# CW308_K82.net
KiCad netlist of a schematic drawn in Altium Designer
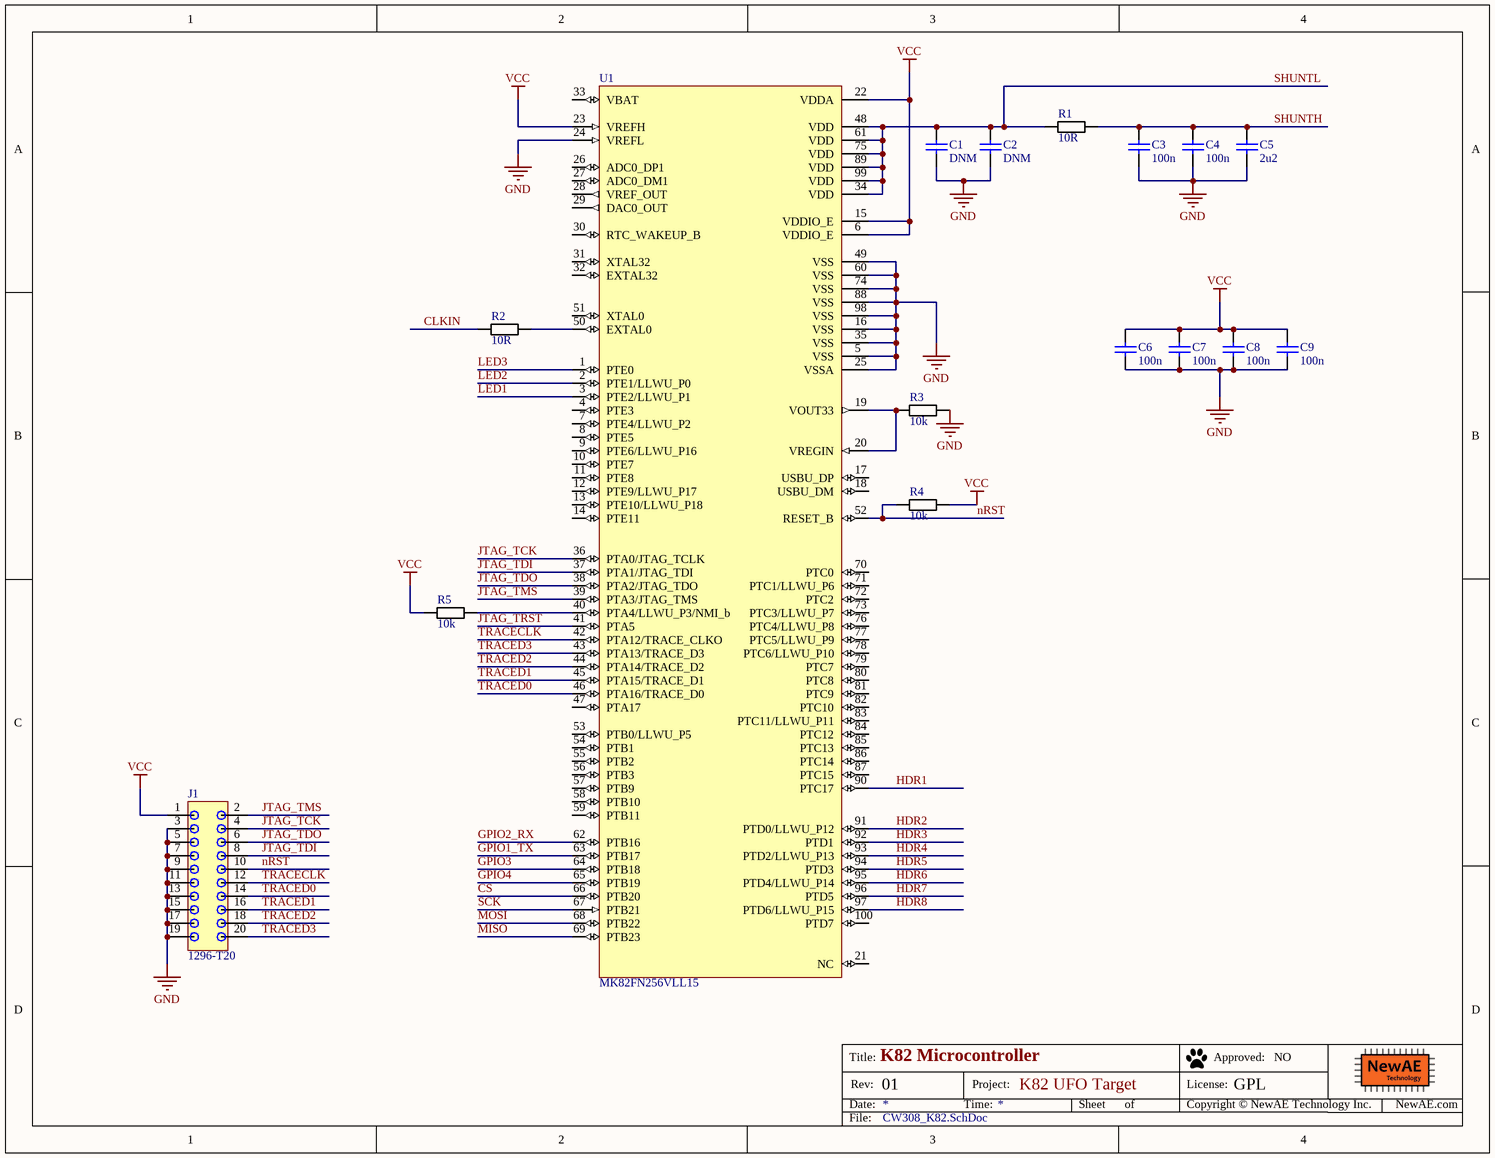
[diagram p0: CW308_K82.SchDoc]

(export (version "E")
  (design (tool "Eeschema 10.0.6"))
  (components
    (comp (ref "C1")
      (value "DNM")
      (footprint "CAPC0603_M")
      (fields (field (name "PART NUMBER") "CCHIP-100n-0603"))
      (libsource (lib "NewAE_AltiumLib") (part "CAP"))
    )
    (comp (ref "C2")
      (value "DNM")
      (footprint "CAPC0603_M")
      (fields (field (name "PART NUMBER") "CCHIP-100n-0603"))
      (libsource (lib "NewAE_AltiumLib") (part "CAP"))
    )
    (comp (ref "C3")
      (value "100n")
      (footprint "CAPC0603_M")
      (description "100n, 0603")
      (fields (field (name "PART NUMBER") "CCHIP-100n-0603"))
      (libsource (lib "NewAE_AltiumLib") (part "CAP"))
    )
    (comp (ref "C4")
      (value "100n")
      (footprint "CAPC0603_M")
      (description "100n, 0603")
      (fields (field (name "PART NUMBER") "CCHIP-100n-0603"))
      (libsource (lib "NewAE_AltiumLib") (part "CAP"))
    )
    (comp (ref "C5")
      (value "2u2")
      (footprint "CAPC0603_M")
      (description "2u2, 0603")
      (fields (field (name "PART NUMBER") "CCHIP-2u2-0603"))
      (libsource (lib "NewAE_AltiumLib") (part "CAP"))
    )
    (comp (ref "C6")
      (value "100n")
      (footprint "CAPC0603_M")
      (description "100n, 0603")
      (fields (field (name "PART NUMBER") "CCHIP-100n-0603"))
      (libsource (lib "NewAE_AltiumLib") (part "CAP"))
    )
    (comp (ref "C7")
      (value "100n")
      (footprint "CAPC0603_M")
      (description "100n, 0603")
      (fields (field (name "PART NUMBER") "CCHIP-100n-0603"))
      (libsource (lib "NewAE_AltiumLib") (part "CAP"))
    )
    (comp (ref "C8")
      (value "100n")
      (footprint "CAPC0603_M")
      (description "100n, 0603")
      (fields (field (name "PART NUMBER") "CCHIP-100n-0603"))
      (libsource (lib "NewAE_AltiumLib") (part "CAP"))
    )
    (comp (ref "C9")
      (value "100n")
      (footprint "CAPC0603_M")
      (description "100n, 0603")
      (fields (field (name "PART NUMBER") "CCHIP-100n-0603"))
      (libsource (lib "NewAE_AltiumLib") (part "CAP"))
    )
    (comp (ref "J1")
      (value "1296-T20")
      (footprint "1296-T20")
      (description "Header, 20-pin, SMD, 0.05\"")
      (libsource (lib "NewAE_AltiumLib") (part "CON20_2ROW"))
    )
    (comp (ref "R1")
      (value "10R")
      (footprint "RESC1608X55N")
      (description "10R res, 0603, 1%, 1/10W")
      (fields (field (name "PART NUMBER") "RCHIP-10R-0603") (field (name "TOLERANCE") "1%"))
      (libsource (lib "NewAE_AltiumLib") (part "RES-EU"))
    )
    (comp (ref "R2")
      (value "10R")
      (footprint "RESC1608X55N")
      (description "10R res, 0603, 1%, 1/10W")
      (fields (field (name "PART NUMBER") "RCHIP-10R-0603") (field (name "TOLERANCE") "1%"))
      (libsource (lib "NewAE_AltiumLib") (part "RES-EU"))
    )
    (comp (ref "R3")
      (value "10k")
      (footprint "RESC1608X55N")
      (description "10k res, 0603, 1%, 1/10W")
      (fields (field (name "PART NUMBER") "RCHIP-10K-0603") (field (name "TOLERANCE") "1%"))
      (libsource (lib "NewAE_AltiumLib") (part "RES-EU"))
    )
    (comp (ref "R4")
      (value "10k")
      (footprint "RESC1608X55N")
      (description "10k res, 0603, 1%, 1/10W")
      (fields (field (name "PART NUMBER") "RCHIP-10K-0603") (field (name "TOLERANCE") "1%"))
      (libsource (lib "NewAE_AltiumLib") (part "RES-EU"))
    )
    (comp (ref "R5")
      (value "10k")
      (footprint "RESC1608X55N")
      (description "10k res, 0603, 1%, 1/10W")
      (fields (field (name "PART NUMBER") "RCHIP-10K-0603") (field (name "TOLERANCE") "1%"))
      (libsource (lib "NewAE_AltiumLib") (part "RES-EU"))
    )
    (comp (ref "U1")
      (value "MK82FN256VLL15")
      (footprint "SQFP50P1600X1600X170-100N")
      (libsource (lib "NewAE_AltiumLib") (part "MK82FN256VLL15"))
    )
  )
  (nets
    (net (code "1") (name "/CLKIN") (class "Default")
      (node (ref "R2") (pin "1") (pinfunction "1_1") (pintype "passive"))
    )
    (net (code "2") (name "/CS") (class "Default")
      (node (ref "U1") (pin "66") (pinfunction "PTB20_66") (pintype "bidirectional"))
    )
    (net (code "3") (name "/GPIO1_TX") (class "Default")
      (node (ref "U1") (pin "63") (pinfunction "PTB17_63") (pintype "bidirectional"))
    )
    (net (code "4") (name "/GPIO2_RX") (class "Default")
      (node (ref "U1") (pin "62") (pinfunction "PTB16_62") (pintype "bidirectional"))
    )
    (net (code "5") (name "/GPIO3") (class "Default")
      (node (ref "U1") (pin "64") (pinfunction "PTB18_64") (pintype "bidirectional"))
    )
    (net (code "6") (name "/GPIO4") (class "Default")
      (node (ref "U1") (pin "65") (pinfunction "PTB19_65") (pintype "bidirectional"))
    )
    (net (code "7") (name "/HDR1") (class "Default")
      (node (ref "U1") (pin "90") (pinfunction "PTC17_90") (pintype "bidirectional"))
    )
    (net (code "8") (name "/HDR2") (class "Default")
      (node (ref "U1") (pin "91") (pinfunction "PTD0/LLWU_P12_91") (pintype "bidirectional"))
    )
    (net (code "9") (name "/HDR3") (class "Default")
      (node (ref "U1") (pin "92") (pinfunction "PTD1_92") (pintype "bidirectional"))
    )
    (net (code "10") (name "/HDR4") (class "Default")
      (node (ref "U1") (pin "93") (pinfunction "PTD2/LLWU_P13_93") (pintype "bidirectional"))
    )
    (net (code "11") (name "/HDR5") (class "Default")
      (node (ref "U1") (pin "94") (pinfunction "PTD3_94") (pintype "bidirectional"))
    )
    (net (code "12") (name "/HDR6") (class "Default")
      (node (ref "U1") (pin "95") (pinfunction "PTD4/LLWU_P14_95") (pintype "bidirectional"))
    )
    (net (code "13") (name "/HDR7") (class "Default")
      (node (ref "U1") (pin "96") (pinfunction "PTD5_96") (pintype "bidirectional"))
    )
    (net (code "14") (name "/HDR8") (class "Default")
      (node (ref "U1") (pin "97") (pinfunction "PTD6/LLWU_P15_97") (pintype "bidirectional"))
    )
    (net (code "15") (name "/JTAG_TCK") (class "Default")
      (node (ref "J1") (pin "4") (pinfunction "4_4") (pintype "passive"))
      (node (ref "U1") (pin "36") (pinfunction "PTA0/JTAG_TCLK_36") (pintype "bidirectional"))
    )
    (net (code "16") (name "/JTAG_TDI") (class "Default")
      (node (ref "J1") (pin "8") (pinfunction "8_8") (pintype "passive"))
      (node (ref "U1") (pin "37") (pinfunction "PTA1/JTAG_TDI_37") (pintype "bidirectional"))
    )
    (net (code "17") (name "/JTAG_TDO") (class "Default")
      (node (ref "J1") (pin "6") (pinfunction "6_6") (pintype "passive"))
      (node (ref "U1") (pin "38") (pinfunction "PTA2/JTAG_TDO_38") (pintype "bidirectional"))
    )
    (net (code "18") (name "/JTAG_TMS") (class "Default")
      (node (ref "J1") (pin "2") (pinfunction "2_2") (pintype "passive"))
      (node (ref "U1") (pin "39") (pinfunction "PTA3/JTAG_TMS_39") (pintype "bidirectional"))
    )
    (net (code "19") (name "/JTAG_TRST") (class "Default")
      (node (ref "U1") (pin "41") (pinfunction "PTA5_41") (pintype "bidirectional"))
    )
    (net (code "20") (name "/LED1") (class "Default")
      (node (ref "U1") (pin "3") (pinfunction "PTE2/LLWU_P1_3") (pintype "bidirectional"))
    )
    (net (code "21") (name "/LED2") (class "Default")
      (node (ref "U1") (pin "2") (pinfunction "PTE1/LLWU_P0_2") (pintype "bidirectional"))
    )
    (net (code "22") (name "/LED3") (class "Default")
      (node (ref "U1") (pin "1") (pinfunction "PTE0_1") (pintype "bidirectional"))
    )
    (net (code "23") (name "/MISO") (class "Default")
      (node (ref "U1") (pin "69") (pinfunction "PTB23_69") (pintype "bidirectional"))
    )
    (net (code "24") (name "/MOSI") (class "Default")
      (node (ref "U1") (pin "68") (pinfunction "PTB22_68") (pintype "bidirectional"))
    )
    (net (code "25") (name "/SCK") (class "Default")
      (node (ref "U1") (pin "67") (pinfunction "PTB21_67") (pintype "input"))
    )
    (net (code "26") (name "/SHUNTH") (class "Default")
      (node (ref "C3") (pin "1") (pinfunction "1_1") (pintype "passive"))
      (node (ref "C4") (pin "1") (pinfunction "1_1") (pintype "passive"))
      (node (ref "C5") (pin "1") (pinfunction "1_1") (pintype "passive"))
      (node (ref "R1") (pin "2") (pinfunction "2_2") (pintype "passive"))
    )
    (net (code "27") (name "/SHUNTL") (class "Default")
      (node (ref "C1") (pin "1") (pinfunction "1_1") (pintype "passive"))
      (node (ref "C2") (pin "1") (pinfunction "1_1") (pintype "passive"))
      (node (ref "R1") (pin "1") (pinfunction "1_1") (pintype "passive"))
      (node (ref "U1") (pin "34") (pinfunction "VDD_34") (pintype "power_in"))
      (node (ref "U1") (pin "48") (pinfunction "VDD_48") (pintype "power_in"))
      (node (ref "U1") (pin "61") (pinfunction "VDD_61") (pintype "power_in"))
      (node (ref "U1") (pin "75") (pinfunction "VDD_75") (pintype "power_in"))
      (node (ref "U1") (pin "89") (pinfunction "VDD_89") (pintype "power_in"))
      (node (ref "U1") (pin "99") (pinfunction "VDD_99") (pintype "power_in"))
    )
    (net (code "28") (name "/TRACECLK") (class "Default")
      (node (ref "J1") (pin "12") (pinfunction "10_12") (pintype "passive"))
      (node (ref "U1") (pin "42") (pinfunction "PTA12/TRACE_CLKO_42") (pintype "bidirectional"))
    )
    (net (code "29") (name "/TRACED0") (class "Default")
      (node (ref "J1") (pin "14") (pinfunction "10_14") (pintype "passive"))
      (node (ref "U1") (pin "46") (pinfunction "PTA16/TRACE_D0_46") (pintype "bidirectional"))
    )
    (net (code "30") (name "/TRACED1") (class "Default")
      (node (ref "J1") (pin "16") (pinfunction "10_16") (pintype "passive"))
      (node (ref "U1") (pin "45") (pinfunction "PTA15/TRACE_D1_45") (pintype "bidirectional"))
    )
    (net (code "31") (name "/TRACED2") (class "Default")
      (node (ref "J1") (pin "18") (pinfunction "10_18") (pintype "passive"))
      (node (ref "U1") (pin "44") (pinfunction "PTA14/TRACE_D2_44") (pintype "bidirectional"))
    )
    (net (code "32") (name "/TRACED3") (class "Default")
      (node (ref "J1") (pin "20") (pinfunction "10_20") (pintype "passive"))
      (node (ref "U1") (pin "43") (pinfunction "PTA13/TRACE_D3_43") (pintype "bidirectional"))
    )
    (net (code "33") (name "/nRST") (class "Default")
      (node (ref "J1") (pin "10") (pinfunction "10_10") (pintype "passive"))
      (node (ref "R4") (pin "1") (pinfunction "1_1") (pintype "passive"))
      (node (ref "U1") (pin "52") (pinfunction "RESET_B_52") (pintype "bidirectional"))
    )
    (net (code "34") (name "GND") (class "Default")
      (node (ref "C1") (pin "2") (pinfunction "2_2") (pintype "passive"))
      (node (ref "C2") (pin "2") (pinfunction "2_2") (pintype "passive"))
      (node (ref "C3") (pin "2") (pinfunction "2_2") (pintype "passive"))
      (node (ref "C4") (pin "2") (pinfunction "2_2") (pintype "passive"))
      (node (ref "C5") (pin "2") (pinfunction "2_2") (pintype "passive"))
      (node (ref "C6") (pin "2") (pinfunction "2_2") (pintype "passive"))
      (node (ref "C7") (pin "2") (pinfunction "2_2") (pintype "passive"))
      (node (ref "C8") (pin "2") (pinfunction "2_2") (pintype "passive"))
      (node (ref "C9") (pin "2") (pinfunction "2_2") (pintype "passive"))
      (node (ref "J1") (pin "11") (pinfunction "9_11") (pintype "passive"))
      (node (ref "J1") (pin "13") (pinfunction "9_13") (pintype "passive"))
      (node (ref "J1") (pin "15") (pinfunction "9_15") (pintype "passive"))
      (node (ref "J1") (pin "17") (pinfunction "9_17") (pintype "passive"))
      (node (ref "J1") (pin "19") (pinfunction "9_19") (pintype "passive"))
      (node (ref "J1") (pin "3") (pinfunction "3_3") (pintype "passive"))
      (node (ref "J1") (pin "5") (pinfunction "5_5") (pintype "passive"))
      (node (ref "J1") (pin "7") (pinfunction "7_7") (pintype "passive"))
      (node (ref "J1") (pin "9") (pinfunction "9_9") (pintype "passive"))
      (node (ref "R3") (pin "2") (pinfunction "2_2") (pintype "passive"))
      (node (ref "U1") (pin "16") (pinfunction "VSS_16") (pintype "power_in"))
      (node (ref "U1") (pin "24") (pinfunction "VREFL_24") (pintype "input"))
      (node (ref "U1") (pin "25") (pinfunction "VSSA_25") (pintype "power_in"))
      (node (ref "U1") (pin "35") (pinfunction "VSS_35") (pintype "power_in"))
      (node (ref "U1") (pin "49") (pinfunction "VSS_49") (pintype "power_in"))
      (node (ref "U1") (pin "5") (pinfunction "VSS_5") (pintype "power_in"))
      (node (ref "U1") (pin "60") (pinfunction "VSS_60") (pintype "power_in"))
      (node (ref "U1") (pin "74") (pinfunction "VSS_74") (pintype "power_in"))
      (node (ref "U1") (pin "88") (pinfunction "VSS_88") (pintype "power_in"))
      (node (ref "U1") (pin "98") (pinfunction "VSS_98") (pintype "power_in"))
    )
    (net (code "35") (name "Net-(U1-EXTAL0)") (class "Default")
      (node (ref "R2") (pin "2") (pinfunction "2_2") (pintype "passive"))
      (node (ref "U1") (pin "50") (pinfunction "EXTAL0_50") (pintype "bidirectional"))
    )
    (net (code "36") (name "Net-(U1-PTA4{slash}LLWU_P3{slash}NMI_b)") (class "Default")
      (node (ref "R5") (pin "2") (pinfunction "2_2") (pintype "passive"))
      (node (ref "U1") (pin "40") (pinfunction "PTA4/LLWU_P3/NMI_b_40") (pintype "bidirectional"))
    )
    (net (code "37") (name "Net-(U1-VOUT33)") (class "Default")
      (node (ref "R3") (pin "1") (pinfunction "1_1") (pintype "passive"))
      (node (ref "U1") (pin "19") (pinfunction "VOUT33_19") (pintype "output"))
      (node (ref "U1") (pin "20") (pinfunction "VREGIN_20") (pintype "input"))
    )
    (net (code "38") (name "VCC") (class "Default")
      (node (ref "C6") (pin "1") (pinfunction "1_1") (pintype "passive"))
      (node (ref "C7") (pin "1") (pinfunction "1_1") (pintype "passive"))
      (node (ref "C8") (pin "1") (pinfunction "1_1") (pintype "passive"))
      (node (ref "C9") (pin "1") (pinfunction "1_1") (pintype "passive"))
      (node (ref "J1") (pin "1") (pinfunction "1_1") (pintype "passive"))
      (node (ref "R4") (pin "2") (pinfunction "2_2") (pintype "passive"))
      (node (ref "R5") (pin "1") (pinfunction "1_1") (pintype "passive"))
      (node (ref "U1") (pin "15") (pinfunction "VDDIO_E_15") (pintype "power_in"))
      (node (ref "U1") (pin "22") (pinfunction "VDDA_22") (pintype "power_in"))
      (node (ref "U1") (pin "23") (pinfunction "VREFH_23") (pintype "input"))
      (node (ref "U1") (pin "6") (pinfunction "VDDIO_E_6") (pintype "power_in"))
    )
    (net (code "39") (name "unconnected-(U1-ADC0_DM1-Pad27)") (class "Default")
      (node (ref "U1") (pin "27") (pinfunction "ADC0_DM1_27") (pintype "bidirectional"))
    )
    (net (code "40") (name "unconnected-(U1-ADC0_DP1-Pad26)") (class "Default")
      (node (ref "U1") (pin "26") (pinfunction "ADC0_DP1_26") (pintype "bidirectional"))
    )
    (net (code "41") (name "unconnected-(U1-DAC0_OUT-Pad29)") (class "Default")
      (node (ref "U1") (pin "29") (pinfunction "DAC0_OUT_29") (pintype "output"))
    )
    (net (code "42") (name "unconnected-(U1-EXTAL32-Pad32)") (class "Default")
      (node (ref "U1") (pin "32") (pinfunction "EXTAL32_32") (pintype "bidirectional"))
    )
    (net (code "43") (name "unconnected-(U1-NC-Pad21)") (class "Default")
      (node (ref "U1") (pin "21") (pinfunction "NC_21") (pintype "bidirectional"))
    )
    (net (code "44") (name "unconnected-(U1-PTA17-Pad47)") (class "Default")
      (node (ref "U1") (pin "47") (pinfunction "PTA17_47") (pintype "bidirectional"))
    )
    (net (code "45") (name "unconnected-(U1-PTB0{slash}LLWU_P5-Pad53)") (class "Default")
      (node (ref "U1") (pin "53") (pinfunction "PTB0/LLWU_P5_53") (pintype "bidirectional"))
    )
    (net (code "46") (name "unconnected-(U1-PTB1-Pad54)") (class "Default")
      (node (ref "U1") (pin "54") (pinfunction "PTB1_54") (pintype "bidirectional"))
    )
    (net (code "47") (name "unconnected-(U1-PTB2-Pad55)") (class "Default")
      (node (ref "U1") (pin "55") (pinfunction "PTB2_55") (pintype "bidirectional"))
    )
    (net (code "48") (name "unconnected-(U1-PTB3-Pad56)") (class "Default")
      (node (ref "U1") (pin "56") (pinfunction "PTB3_56") (pintype "bidirectional"))
    )
    (net (code "49") (name "unconnected-(U1-PTB9-Pad57)") (class "Default")
      (node (ref "U1") (pin "57") (pinfunction "PTB9_57") (pintype "bidirectional"))
    )
    (net (code "50") (name "unconnected-(U1-PTB10-Pad58)") (class "Default")
      (node (ref "U1") (pin "58") (pinfunction "PTB10_58") (pintype "bidirectional"))
    )
    (net (code "51") (name "unconnected-(U1-PTB11-Pad59)") (class "Default")
      (node (ref "U1") (pin "59") (pinfunction "PTB11_59") (pintype "bidirectional"))
    )
    (net (code "52") (name "unconnected-(U1-PTC0-Pad70)") (class "Default")
      (node (ref "U1") (pin "70") (pinfunction "PTC0_70") (pintype "bidirectional"))
    )
    (net (code "53") (name "unconnected-(U1-PTC1{slash}LLWU_P6-Pad71)") (class "Default")
      (node (ref "U1") (pin "71") (pinfunction "PTC1/LLWU_P6_71") (pintype "bidirectional"))
    )
    (net (code "54") (name "unconnected-(U1-PTC2-Pad72)") (class "Default")
      (node (ref "U1") (pin "72") (pinfunction "PTC2_72") (pintype "bidirectional"))
    )
    (net (code "55") (name "unconnected-(U1-PTC3{slash}LLWU_P7-Pad73)") (class "Default")
      (node (ref "U1") (pin "73") (pinfunction "PTC3/LLWU_P7_73") (pintype "bidirectional"))
    )
    (net (code "56") (name "unconnected-(U1-PTC4{slash}LLWU_P8-Pad76)") (class "Default")
      (node (ref "U1") (pin "76") (pinfunction "PTC4/LLWU_P8_76") (pintype "bidirectional"))
    )
    (net (code "57") (name "unconnected-(U1-PTC5{slash}LLWU_P9-Pad77)") (class "Default")
      (node (ref "U1") (pin "77") (pinfunction "PTC5/LLWU_P9_77") (pintype "bidirectional"))
    )
    (net (code "58") (name "unconnected-(U1-PTC6{slash}LLWU_P10-Pad78)") (class "Default")
      (node (ref "U1") (pin "78") (pinfunction "PTC6/LLWU_P10_78") (pintype "bidirectional"))
    )
    (net (code "59") (name "unconnected-(U1-PTC7-Pad79)") (class "Default")
      (node (ref "U1") (pin "79") (pinfunction "PTC7_79") (pintype "bidirectional"))
    )
    (net (code "60") (name "unconnected-(U1-PTC8-Pad80)") (class "Default")
      (node (ref "U1") (pin "80") (pinfunction "PTC8_80") (pintype "bidirectional"))
    )
    (net (code "61") (name "unconnected-(U1-PTC9-Pad81)") (class "Default")
      (node (ref "U1") (pin "81") (pinfunction "PTC9_81") (pintype "bidirectional"))
    )
    (net (code "62") (name "unconnected-(U1-PTC10-Pad82)") (class "Default")
      (node (ref "U1") (pin "82") (pinfunction "PTC10_82") (pintype "bidirectional"))
    )
    (net (code "63") (name "unconnected-(U1-PTC11{slash}LLWU_P11-Pad83)") (class "Default")
      (node (ref "U1") (pin "83") (pinfunction "PTC11/LLWU_P11_83") (pintype "bidirectional"))
    )
    (net (code "64") (name "unconnected-(U1-PTC12-Pad84)") (class "Default")
      (node (ref "U1") (pin "84") (pinfunction "PTC12_84") (pintype "bidirectional"))
    )
    (net (code "65") (name "unconnected-(U1-PTC13-Pad85)") (class "Default")
      (node (ref "U1") (pin "85") (pinfunction "PTC13_85") (pintype "bidirectional"))
    )
    (net (code "66") (name "unconnected-(U1-PTC14-Pad86)") (class "Default")
      (node (ref "U1") (pin "86") (pinfunction "PTC14_86") (pintype "bidirectional"))
    )
    (net (code "67") (name "unconnected-(U1-PTC15-Pad87)") (class "Default")
      (node (ref "U1") (pin "87") (pinfunction "PTC15_87") (pintype "bidirectional"))
    )
    (net (code "68") (name "unconnected-(U1-PTD7-Pad100)") (class "Default")
      (node (ref "U1") (pin "100") (pinfunction "PTD7_100") (pintype "bidirectional"))
    )
    (net (code "69") (name "unconnected-(U1-PTE3-Pad4)") (class "Default")
      (node (ref "U1") (pin "4") (pinfunction "PTE3_4") (pintype "bidirectional"))
    )
    (net (code "70") (name "unconnected-(U1-PTE4{slash}LLWU_P2-Pad7)") (class "Default")
      (node (ref "U1") (pin "7") (pinfunction "PTE4/LLWU_P2_7") (pintype "bidirectional"))
    )
    (net (code "71") (name "unconnected-(U1-PTE5-Pad8)") (class "Default")
      (node (ref "U1") (pin "8") (pinfunction "PTE5_8") (pintype "bidirectional"))
    )
    (net (code "72") (name "unconnected-(U1-PTE6{slash}LLWU_P16-Pad9)") (class "Default")
      (node (ref "U1") (pin "9") (pinfunction "PTE6/LLWU_P16_9") (pintype "bidirectional"))
    )
    (net (code "73") (name "unconnected-(U1-PTE7-Pad10)") (class "Default")
      (node (ref "U1") (pin "10") (pinfunction "PTE7_10") (pintype "bidirectional"))
    )
    (net (code "74") (name "unconnected-(U1-PTE8-Pad11)") (class "Default")
      (node (ref "U1") (pin "11") (pinfunction "PTE8_11") (pintype "bidirectional"))
    )
    (net (code "75") (name "unconnected-(U1-PTE9{slash}LLWU_P17-Pad12)") (class "Default")
      (node (ref "U1") (pin "12") (pinfunction "PTE9/LLWU_P17_12") (pintype "bidirectional"))
    )
    (net (code "76") (name "unconnected-(U1-PTE10{slash}LLWU_P18-Pad13)") (class "Default")
      (node (ref "U1") (pin "13") (pinfunction "PTE10/LLWU_P18_13") (pintype "bidirectional"))
    )
    (net (code "77") (name "unconnected-(U1-PTE11-Pad14)") (class "Default")
      (node (ref "U1") (pin "14") (pinfunction "PTE11_14") (pintype "bidirectional"))
    )
    (net (code "78") (name "unconnected-(U1-RTC_WAKEUP_B-Pad30)") (class "Default")
      (node (ref "U1") (pin "30") (pinfunction "RTC_WAKEUP_B_30") (pintype "bidirectional"))
    )
    (net (code "79") (name "unconnected-(U1-USBU_DM-Pad18)") (class "Default")
      (node (ref "U1") (pin "18") (pinfunction "USBU_DM_18") (pintype "bidirectional"))
    )
    (net (code "80") (name "unconnected-(U1-USBU_DP-Pad17)") (class "Default")
      (node (ref "U1") (pin "17") (pinfunction "USBU_DP_17") (pintype "bidirectional"))
    )
    (net (code "81") (name "unconnected-(U1-VBAT-Pad33)") (class "Default")
      (node (ref "U1") (pin "33") (pinfunction "VBAT_33") (pintype "bidirectional"))
    )
    (net (code "82") (name "unconnected-(U1-VREF_OUT-Pad28)") (class "Default")
      (node (ref "U1") (pin "28") (pinfunction "VREF_OUT_28") (pintype "output"))
    )
    (net (code "83") (name "unconnected-(U1-XTAL0-Pad51)") (class "Default")
      (node (ref "U1") (pin "51") (pinfunction "XTAL0_51") (pintype "bidirectional"))
    )
    (net (code "84") (name "unconnected-(U1-XTAL32-Pad31)") (class "Default")
      (node (ref "U1") (pin "31") (pinfunction "XTAL32_31") (pintype "bidirectional"))
    )
  )
)
